# BiaBoard.net
KiCad netlist of a schematic drawn in EAGLE
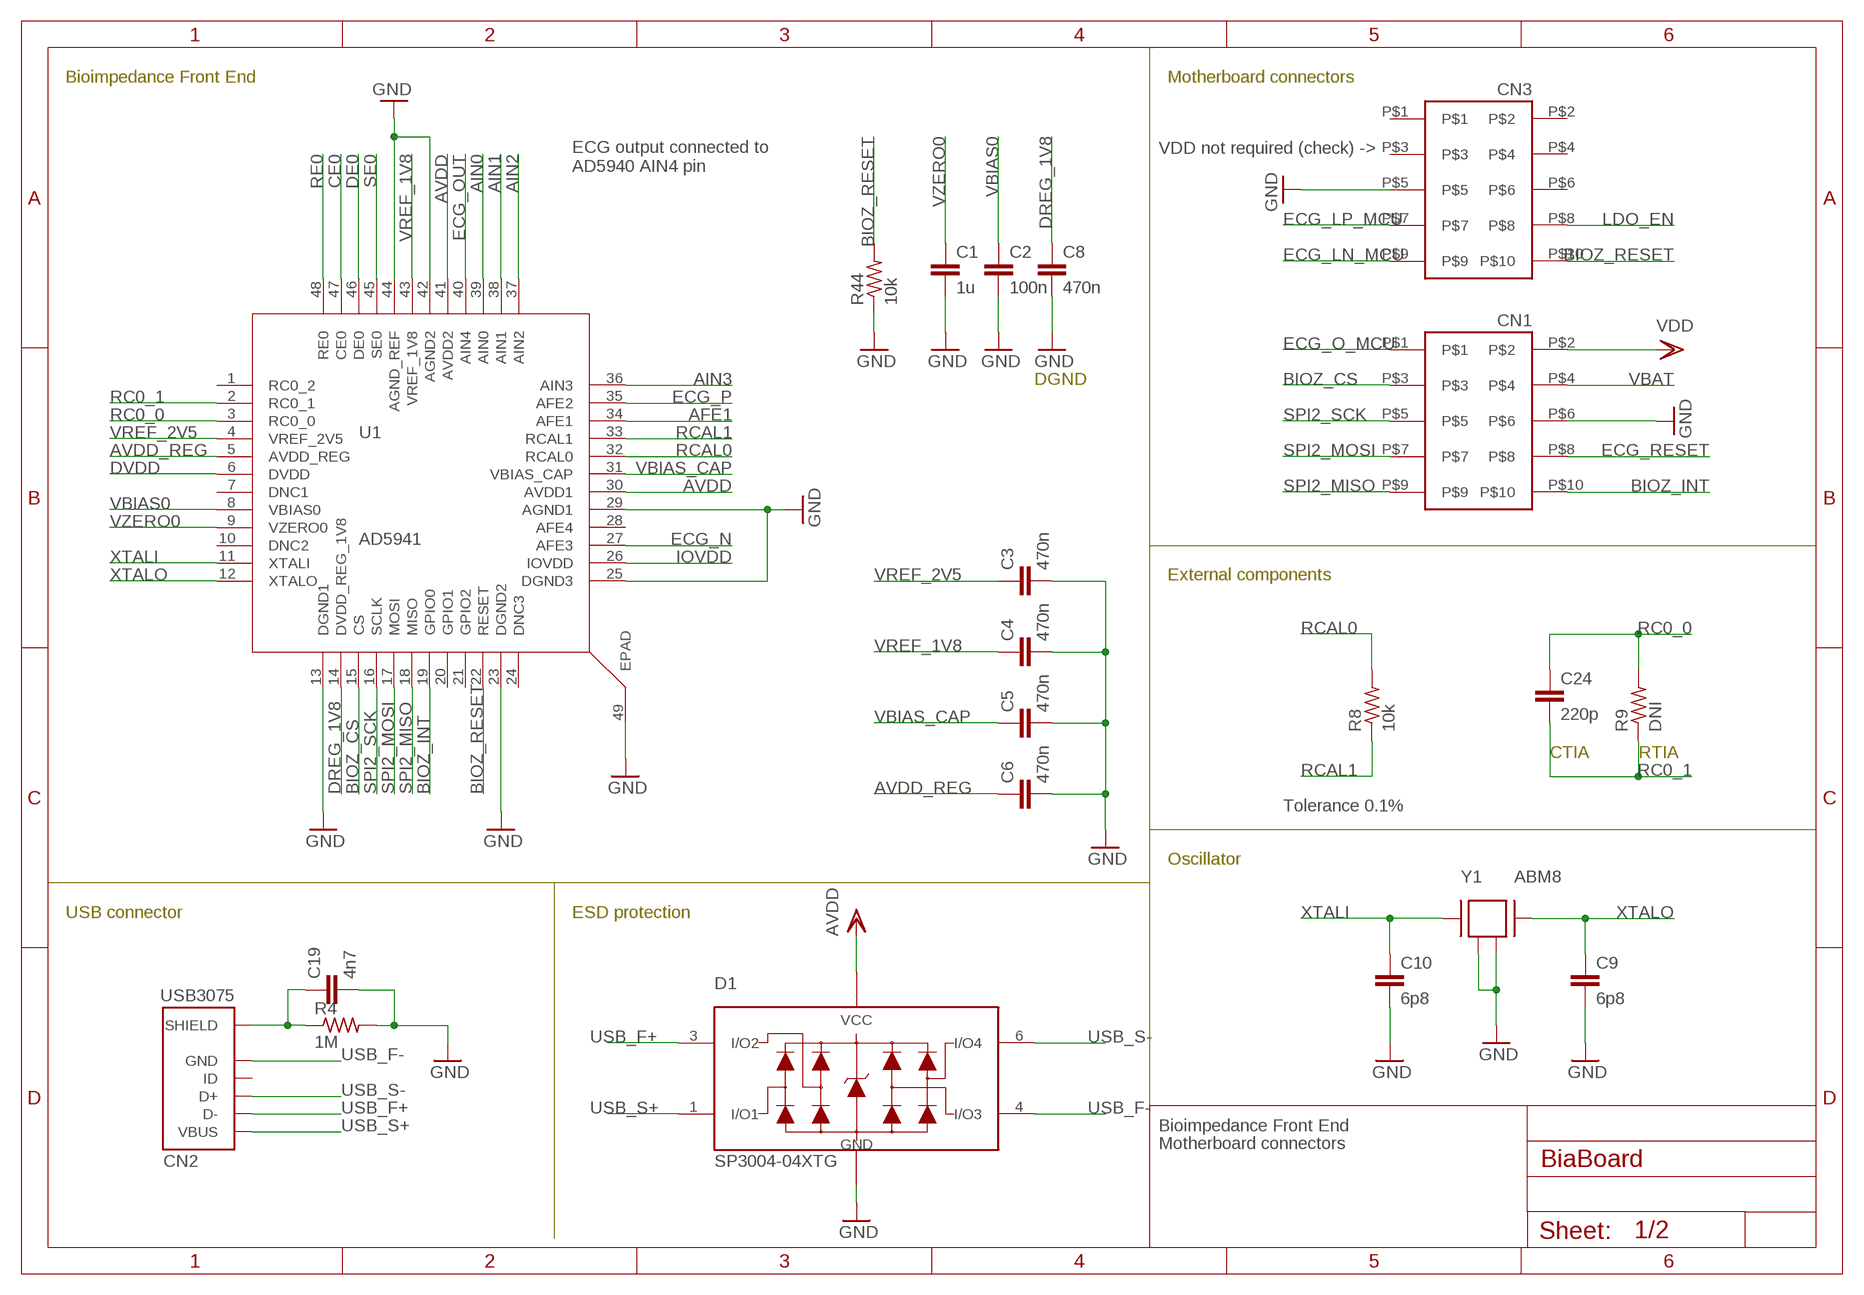
[diagram p0: schematic, sheet 1]
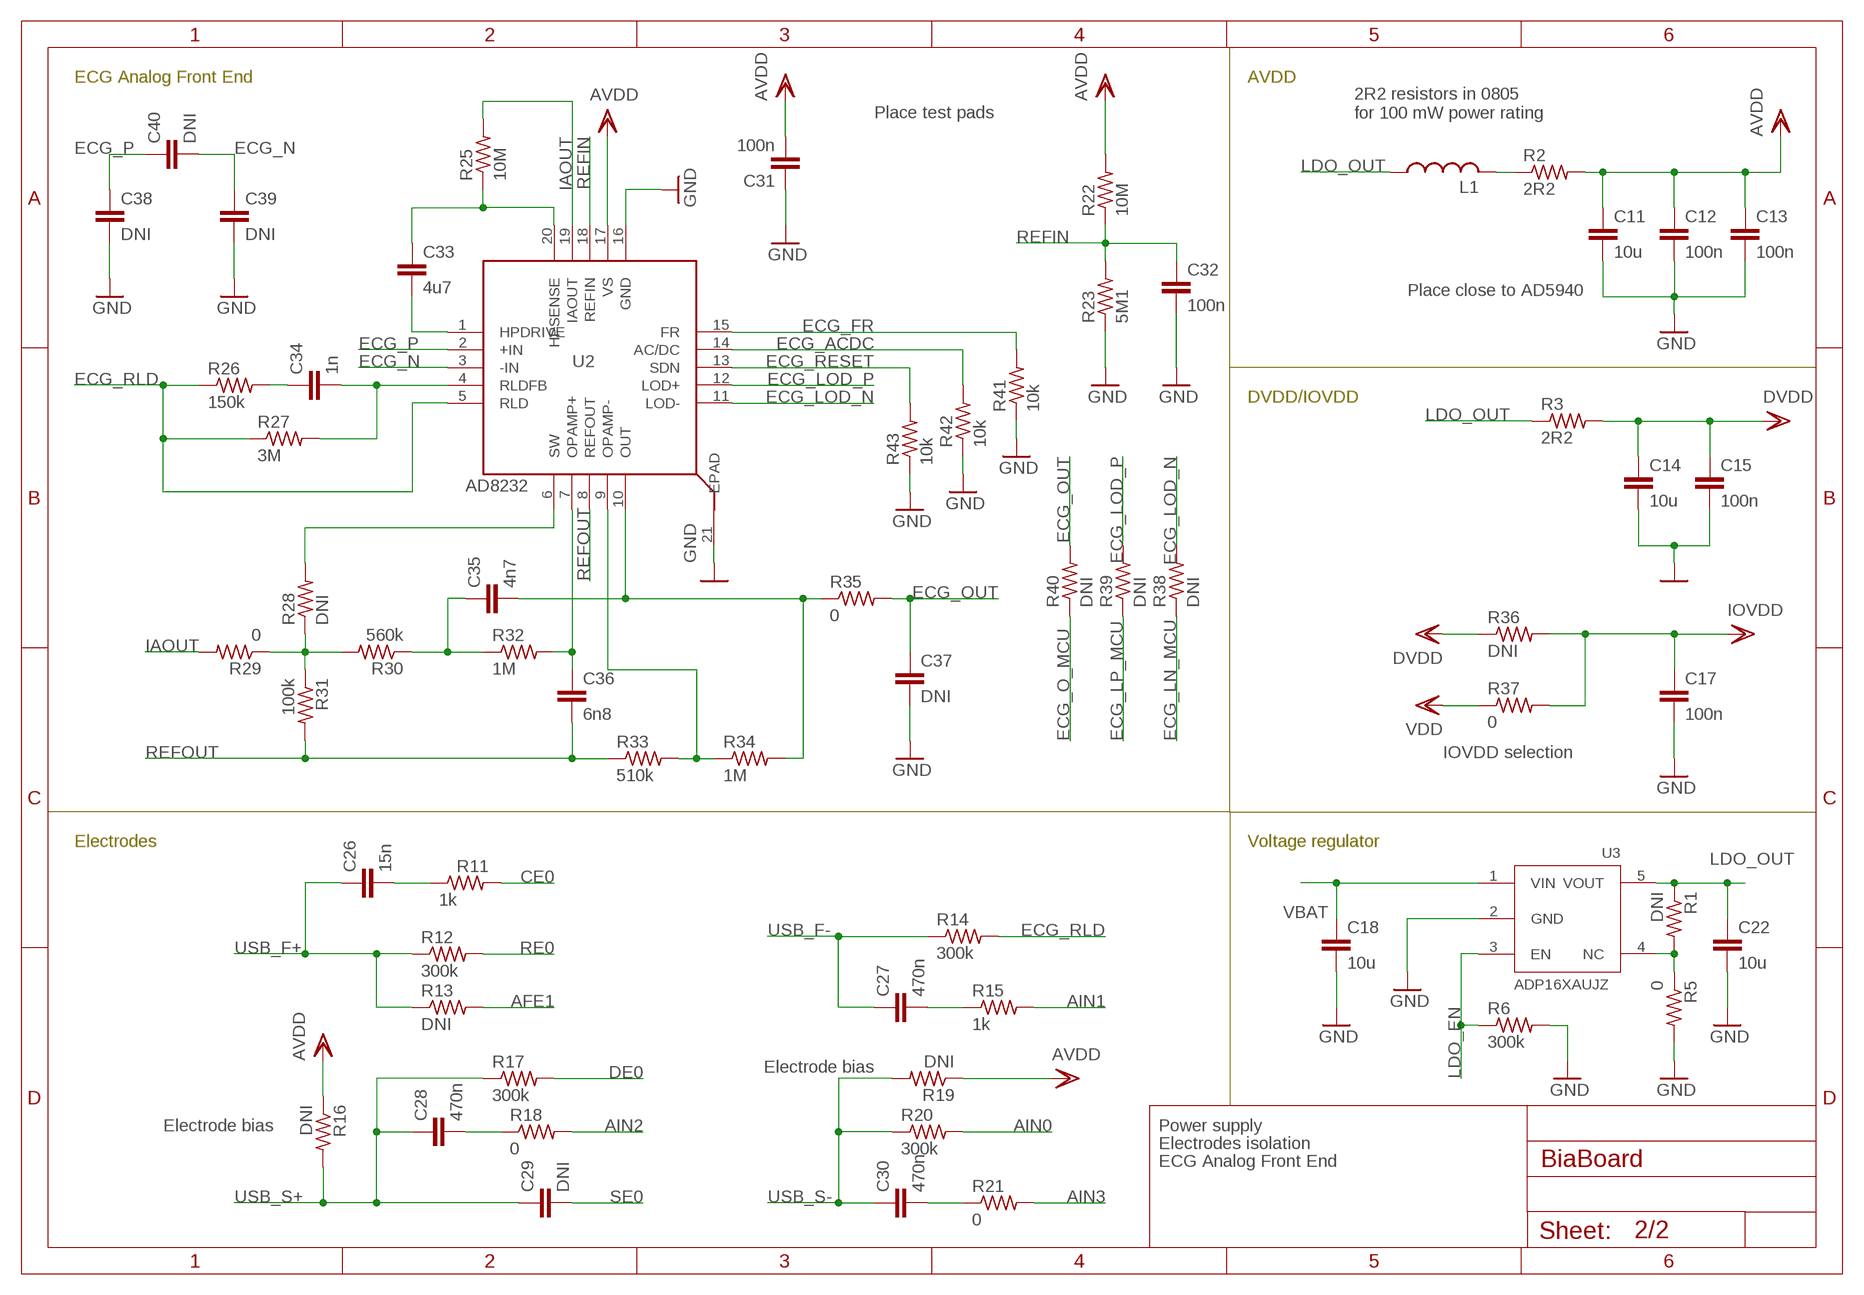
[diagram p1: schematic, sheet 2]

(export (version "E")
  (design (tool "Eeschema 10.0.6"))
  (components
    (comp (ref "C1")
      (value "1u")
      (footprint "eagle-import:C0402")
      (libsource (lib "eagle-import") (part "C0402"))
    )
    (comp (ref "C2")
      (value "100n")
      (footprint "eagle-import:C0402")
      (libsource (lib "eagle-import") (part "C0402"))
    )
    (comp (ref "C3")
      (value "470n")
      (footprint "eagle-import:C0402")
      (libsource (lib "eagle-import") (part "C0402"))
    )
    (comp (ref "C4")
      (value "470n")
      (footprint "eagle-import:C0402")
      (libsource (lib "eagle-import") (part "C0402"))
    )
    (comp (ref "C5")
      (value "470n")
      (footprint "eagle-import:C0402")
      (libsource (lib "eagle-import") (part "C0402"))
    )
    (comp (ref "C6")
      (value "470n")
      (footprint "eagle-import:C0402")
      (libsource (lib "eagle-import") (part "C0402"))
    )
    (comp (ref "C8")
      (value "470n")
      (footprint "eagle-import:C0402")
      (libsource (lib "eagle-import") (part "C0402"))
    )
    (comp (ref "C9")
      (value "6p8")
      (footprint "eagle-import:C0402")
      (libsource (lib "eagle-import") (part "C0402"))
    )
    (comp (ref "C10")
      (value "6p8")
      (footprint "eagle-import:C0402")
      (libsource (lib "eagle-import") (part "C0402"))
    )
    (comp (ref "C19")
      (value "4n7")
      (footprint "eagle-import:C0402")
      (libsource (lib "eagle-import") (part "C0402"))
    )
    (comp (ref "C24")
      (value "220p")
      (footprint "eagle-import:C0402")
      (libsource (lib "eagle-import") (part "C0402"))
    )
    (comp (ref "CN1")
      (value "FTSH-105TO")
      (footprint "eagle-import:FTSH-105-D")
      (libsource (lib "eagle-import") (part "FTSH-105TO"))
    )
    (comp (ref "CN2")
      (value "USB3075")
      (footprint "eagle-import:USB3075")
      (libsource (lib "eagle-import") (part "USB3075"))
    )
    (comp (ref "CN3")
      (value "FTSH-105TO")
      (footprint "eagle-import:FTSH-105-D")
      (libsource (lib "eagle-import") (part "FTSH-105TO"))
    )
    (comp (ref "D1")
      (value "SP3004-04XTG")
      (footprint "eagle-import:SOT50P160X60-6N")
      (libsource (lib "eagle-import") (part "SP3004-04XTG"))
    )
    (comp (ref "R4")
      (value "1M")
      (footprint "eagle-import:0402")
      (libsource (lib "eagle-import") (part "R0402"))
    )
    (comp (ref "R8")
      (value "10k")
      (footprint "eagle-import:0402")
      (fields (field (name "TOLERANCE") "0.1%"))
      (libsource (lib "eagle-import") (part "R0402"))
    )
    (comp (ref "R9")
      (value "DNI")
      (footprint "eagle-import:0402")
      (libsource (lib "eagle-import") (part "R0402"))
    )
    (comp (ref "R44")
      (value "10k")
      (footprint "eagle-import:0402")
      (libsource (lib "eagle-import") (part "R0402"))
    )
    (comp (ref "U1")
      (value "AD5941")
      (footprint "eagle-import:QFN50P700X700X80-49T510N")
      (libsource (lib "eagle-import") (part "AD5941"))
    )
    (comp (ref "Y1")
      (value "ABM8")
      (footprint "eagle-import:ABM8")
      (libsource (lib "eagle-import") (part "ABM8"))
    )
    (comp (ref "C11")
      (value "10u")
      (footprint "eagle-import:C0603")
      (libsource (lib "eagle-import") (part "C0603"))
    )
    (comp (ref "C12")
      (value "100n")
      (footprint "eagle-import:C0402")
      (libsource (lib "eagle-import") (part "C0402"))
    )
    (comp (ref "C13")
      (value "100n")
      (footprint "eagle-import:C0402")
      (libsource (lib "eagle-import") (part "C0402"))
    )
    (comp (ref "C14")
      (value "10u")
      (footprint "eagle-import:C0603")
      (libsource (lib "eagle-import") (part "C0603"))
    )
    (comp (ref "C15")
      (value "100n")
      (footprint "eagle-import:C0402")
      (libsource (lib "eagle-import") (part "C0402"))
    )
    (comp (ref "C17")
      (value "100n")
      (footprint "eagle-import:C0402")
      (libsource (lib "eagle-import") (part "C0402"))
    )
    (comp (ref "C18")
      (value "10u")
      (footprint "eagle-import:C0603")
      (libsource (lib "eagle-import") (part "C0603"))
    )
    (comp (ref "C22")
      (value "10u")
      (footprint "eagle-import:C0603")
      (libsource (lib "eagle-import") (part "C0603"))
    )
    (comp (ref "C26")
      (value "15n")
      (footprint "eagle-import:C0402")
      (libsource (lib "eagle-import") (part "C0402"))
    )
    (comp (ref "C27")
      (value "470n")
      (footprint "eagle-import:C0402")
      (libsource (lib "eagle-import") (part "C0402"))
    )
    (comp (ref "C28")
      (value "470n")
      (footprint "eagle-import:C0402")
      (libsource (lib "eagle-import") (part "C0402"))
    )
    (comp (ref "C29")
      (value "DNI")
      (footprint "eagle-import:C0402")
      (libsource (lib "eagle-import") (part "C0402"))
    )
    (comp (ref "C30")
      (value "470n")
      (footprint "eagle-import:C0402")
      (libsource (lib "eagle-import") (part "C0402"))
    )
    (comp (ref "C31")
      (value "100n")
      (footprint "eagle-import:C0402")
      (libsource (lib "eagle-import") (part "C0402"))
    )
    (comp (ref "C32")
      (value "100n")
      (footprint "eagle-import:C0402")
      (libsource (lib "eagle-import") (part "C0402"))
    )
    (comp (ref "C33")
      (value "4u7")
      (footprint "eagle-import:C0402")
      (libsource (lib "eagle-import") (part "C0402"))
    )
    (comp (ref "C34")
      (value "1n")
      (footprint "eagle-import:C0402")
      (libsource (lib "eagle-import") (part "C0402"))
    )
    (comp (ref "C35")
      (value "4n7")
      (footprint "eagle-import:C0402")
      (libsource (lib "eagle-import") (part "C0402"))
    )
    (comp (ref "C36")
      (value "6n8")
      (footprint "eagle-import:C0402")
      (libsource (lib "eagle-import") (part "C0402"))
    )
    (comp (ref "C37")
      (value "DNI")
      (footprint "eagle-import:C0603")
      (libsource (lib "eagle-import") (part "C0603"))
    )
    (comp (ref "C38")
      (value "DNI")
      (footprint "eagle-import:C0402")
      (libsource (lib "eagle-import") (part "C0402"))
    )
    (comp (ref "C39")
      (value "DNI")
      (footprint "eagle-import:C0402")
      (libsource (lib "eagle-import") (part "C0402"))
    )
    (comp (ref "C40")
      (value "DNI")
      (footprint "eagle-import:C0402")
      (libsource (lib "eagle-import") (part "C0402"))
    )
    (comp (ref "L1")
      (value "L0603")
      (footprint "eagle-import:0603")
      (libsource (lib "eagle-import") (part "L0603"))
    )
    (comp (ref "R1")
      (value "DNI")
      (footprint "eagle-import:0402")
      (libsource (lib "eagle-import") (part "R0402"))
    )
    (comp (ref "R2")
      (value "2R2")
      (footprint "eagle-import:0805")
      (libsource (lib "eagle-import") (part "R0805"))
    )
    (comp (ref "R3")
      (value "2R2")
      (footprint "eagle-import:0805")
      (libsource (lib "eagle-import") (part "R0805"))
    )
    (comp (ref "R5")
      (value "0")
      (footprint "eagle-import:0402")
      (libsource (lib "eagle-import") (part "R0402"))
    )
    (comp (ref "R6")
      (value "300k")
      (footprint "eagle-import:0402")
      (libsource (lib "eagle-import") (part "R0402"))
    )
    (comp (ref "R11")
      (value "1k")
      (footprint "eagle-import:0402")
      (libsource (lib "eagle-import") (part "R0402"))
    )
    (comp (ref "R12")
      (value "300k")
      (footprint "eagle-import:0402")
      (libsource (lib "eagle-import") (part "R0402"))
    )
    (comp (ref "R13")
      (value "DNI")
      (footprint "eagle-import:0402")
      (libsource (lib "eagle-import") (part "R0402"))
    )
    (comp (ref "R14")
      (value "300k")
      (footprint "eagle-import:0402")
      (libsource (lib "eagle-import") (part "R0402"))
    )
    (comp (ref "R15")
      (value "1k")
      (footprint "eagle-import:0402")
      (libsource (lib "eagle-import") (part "R0402"))
    )
    (comp (ref "R16")
      (value "DNI")
      (footprint "eagle-import:0402")
      (libsource (lib "eagle-import") (part "R0402"))
    )
    (comp (ref "R17")
      (value "300k")
      (footprint "eagle-import:0402")
      (libsource (lib "eagle-import") (part "R0402"))
    )
    (comp (ref "R18")
      (value "0")
      (footprint "eagle-import:0402")
      (libsource (lib "eagle-import") (part "R0402"))
    )
    (comp (ref "R19")
      (value "DNI")
      (footprint "eagle-import:0402")
      (libsource (lib "eagle-import") (part "R0402"))
    )
    (comp (ref "R20")
      (value "300k")
      (footprint "eagle-import:0402")
      (libsource (lib "eagle-import") (part "R0402"))
    )
    (comp (ref "R21")
      (value "0")
      (footprint "eagle-import:0402")
      (libsource (lib "eagle-import") (part "R0402"))
    )
    (comp (ref "R22")
      (value "10M")
      (footprint "eagle-import:0402")
      (libsource (lib "eagle-import") (part "R0402"))
    )
    (comp (ref "R23")
      (value "5M1")
      (footprint "eagle-import:0402")
      (libsource (lib "eagle-import") (part "R0402"))
    )
    (comp (ref "R25")
      (value "10M")
      (footprint "eagle-import:0402")
      (libsource (lib "eagle-import") (part "R0402"))
    )
    (comp (ref "R26")
      (value "150k")
      (footprint "eagle-import:0402")
      (libsource (lib "eagle-import") (part "R0402"))
    )
    (comp (ref "R27")
      (value "3M")
      (footprint "eagle-import:0402")
      (libsource (lib "eagle-import") (part "R0402"))
    )
    (comp (ref "R28")
      (value "DNI")
      (footprint "eagle-import:0402")
      (libsource (lib "eagle-import") (part "R0402"))
    )
    (comp (ref "R29")
      (value "0")
      (footprint "eagle-import:0402")
      (libsource (lib "eagle-import") (part "R0402"))
    )
    (comp (ref "R30")
      (value "560k")
      (footprint "eagle-import:0402")
      (libsource (lib "eagle-import") (part "R0402"))
    )
    (comp (ref "R31")
      (value "100k")
      (footprint "eagle-import:0603")
      (libsource (lib "eagle-import") (part "R0603"))
    )
    (comp (ref "R32")
      (value "1M")
      (footprint "eagle-import:0402")
      (libsource (lib "eagle-import") (part "R0402"))
    )
    (comp (ref "R33")
      (value "510k")
      (footprint "eagle-import:0402")
      (libsource (lib "eagle-import") (part "R0402"))
    )
    (comp (ref "R34")
      (value "1M")
      (footprint "eagle-import:0402")
      (libsource (lib "eagle-import") (part "R0402"))
    )
    (comp (ref "R35")
      (value "0")
      (footprint "eagle-import:0402")
      (libsource (lib "eagle-import") (part "R0402"))
    )
    (comp (ref "R36")
      (value "DNI")
      (footprint "eagle-import:0402")
      (libsource (lib "eagle-import") (part "R0402"))
    )
    (comp (ref "R37")
      (value "0")
      (footprint "eagle-import:0402")
      (libsource (lib "eagle-import") (part "R0402"))
    )
    (comp (ref "R38")
      (value "DNI")
      (footprint "eagle-import:0402")
      (libsource (lib "eagle-import") (part "R0402"))
    )
    (comp (ref "R39")
      (value "DNI")
      (footprint "eagle-import:0402")
      (libsource (lib "eagle-import") (part "R0402"))
    )
    (comp (ref "R40")
      (value "DNI")
      (footprint "eagle-import:0402")
      (libsource (lib "eagle-import") (part "R0402"))
    )
    (comp (ref "R41")
      (value "10k")
      (footprint "eagle-import:0402")
      (libsource (lib "eagle-import") (part "R0402"))
    )
    (comp (ref "R42")
      (value "10k")
      (footprint "eagle-import:0402")
      (libsource (lib "eagle-import") (part "R0402"))
    )
    (comp (ref "R43")
      (value "10k")
      (footprint "eagle-import:0402")
      (libsource (lib "eagle-import") (part "R0402"))
    )
    (comp (ref "U2")
      (value "AD8232")
      (footprint "eagle-import:QFN50P400X400X75-21T260N")
      (libsource (lib "eagle-import") (part "AD8232"))
    )
    (comp (ref "U3")
      (value "ADP16XAUJZ")
      (footprint "eagle-import:TSOT23-5L")
      (libsource (lib "eagle-import") (part "ADP16XAUJZ"))
    )
  )
  (nets
    (net (code "1") (name "AFE1") (class "Default")
      (node (ref "R13") (pin "P$2") (pinfunction "2_P$2") (pintype "passive"))
      (node (ref "U1") (pin "34") (pinfunction "AFE1_34") (pintype "bidirectional"))
    )
    (net (code "2") (name "AIN0") (class "Default")
      (node (ref "R20") (pin "P$2") (pinfunction "2_P$2") (pintype "passive"))
      (node (ref "U1") (pin "39") (pinfunction "AIN0_39") (pintype "bidirectional"))
    )
    (net (code "3") (name "AIN1") (class "Default")
      (node (ref "R15") (pin "P$2") (pinfunction "2_P$2") (pintype "passive"))
      (node (ref "U1") (pin "38") (pinfunction "AIN1_38") (pintype "bidirectional"))
    )
    (net (code "4") (name "AIN2") (class "Default")
      (node (ref "R18") (pin "P$2") (pinfunction "2_P$2") (pintype "passive"))
      (node (ref "U1") (pin "37") (pinfunction "AIN2_37") (pintype "bidirectional"))
    )
    (net (code "5") (name "AIN3") (class "Default")
      (node (ref "R21") (pin "P$2") (pinfunction "2_P$2") (pintype "passive"))
      (node (ref "U1") (pin "36") (pinfunction "AIN3_36") (pintype "bidirectional"))
    )
    (net (code "6") (name "AVDD") (class "Default")
      (node (ref "C11") (pin "P$1") (pinfunction "1_P$1") (pintype "passive"))
      (node (ref "C12") (pin "P$1") (pinfunction "1_P$1") (pintype "passive"))
      (node (ref "C13") (pin "P$1") (pinfunction "1_P$1") (pintype "passive"))
      (node (ref "C31") (pin "P$2") (pinfunction "2_P$2") (pintype "passive"))
      (node (ref "D1") (pin "5") (pinfunction "VCC_5") (pintype "bidirectional"))
      (node (ref "R16") (pin "P$1") (pinfunction "1_P$1") (pintype "passive"))
      (node (ref "R19") (pin "P$1") (pinfunction "1_P$1") (pintype "passive"))
      (node (ref "R2") (pin "P$2") (pinfunction "2_P$2") (pintype "passive"))
      (node (ref "R22") (pin "P$2") (pinfunction "2_P$2") (pintype "passive"))
      (node (ref "U1") (pin "30") (pinfunction "AVDD1_30") (pintype "bidirectional"))
      (node (ref "U1") (pin "41") (pinfunction "AVDD2_41") (pintype "bidirectional"))
      (node (ref "U2") (pin "17") (pinfunction "VS_17") (pintype "bidirectional"))
    )
    (net (code "7") (name "AVDD_REG") (class "Default")
      (node (ref "C6") (pin "P$1") (pinfunction "1_P$1") (pintype "passive"))
      (node (ref "U1") (pin "5") (pinfunction "AVDD_REG_5") (pintype "bidirectional"))
    )
    (net (code "8") (name "BIOZ_CS") (class "Default")
      (node (ref "CN1") (pin "P$3") (pinfunction "P$3_P$3") (pintype "bidirectional"))
      (node (ref "U1") (pin "15") (pinfunction "CS_15") (pintype "bidirectional"))
    )
    (net (code "9") (name "BIOZ_INT") (class "Default")
      (node (ref "CN1") (pin "P$10") (pinfunction "P$10_P$10") (pintype "bidirectional"))
      (node (ref "U1") (pin "19") (pinfunction "GPIO0_19") (pintype "bidirectional"))
    )
    (net (code "10") (name "BIOZ_RESET") (class "Default")
      (node (ref "CN3") (pin "P$10") (pinfunction "P$10_P$10") (pintype "bidirectional"))
      (node (ref "R44") (pin "P$2") (pinfunction "2_P$2") (pintype "passive"))
      (node (ref "U1") (pin "22") (pinfunction "RESET_22") (pintype "bidirectional"))
    )
    (net (code "11") (name "CE0") (class "Default")
      (node (ref "R11") (pin "P$2") (pinfunction "2_P$2") (pintype "passive"))
      (node (ref "U1") (pin "47") (pinfunction "CE0_47") (pintype "bidirectional"))
    )
    (net (code "12") (name "DE0") (class "Default")
      (node (ref "R17") (pin "P$2") (pinfunction "2_P$2") (pintype "passive"))
      (node (ref "U1") (pin "46") (pinfunction "DE0_46") (pintype "bidirectional"))
    )
    (net (code "13") (name "DREG_1V8") (class "Default")
      (node (ref "C8") (pin "P$1") (pinfunction "1_P$1") (pintype "passive"))
      (node (ref "U1") (pin "14") (pinfunction "DVDD_REG_1V8_14") (pintype "bidirectional"))
    )
    (net (code "14") (name "DVDD") (class "Default")
      (node (ref "C14") (pin "P$1") (pinfunction "1_P$1") (pintype "passive"))
      (node (ref "C15") (pin "P$1") (pinfunction "1_P$1") (pintype "passive"))
      (node (ref "R3") (pin "P$2") (pinfunction "2_P$2") (pintype "passive"))
      (node (ref "R36") (pin "P$1") (pinfunction "1_P$1") (pintype "passive"))
      (node (ref "U1") (pin "6") (pinfunction "DVDD_6") (pintype "bidirectional"))
    )
    (net (code "15") (name "ECG_ACDC") (class "Default")
      (node (ref "R42") (pin "P$2") (pinfunction "2_P$2") (pintype "passive"))
      (node (ref "U2") (pin "14") (pinfunction "AC/DC_14") (pintype "bidirectional"))
    )
    (net (code "16") (name "ECG_FR") (class "Default")
      (node (ref "R41") (pin "P$2") (pinfunction "2_P$2") (pintype "passive"))
      (node (ref "U2") (pin "15") (pinfunction "FR_15") (pintype "bidirectional"))
    )
    (net (code "17") (name "ECG_LN_MCU") (class "Default")
      (node (ref "CN3") (pin "P$9") (pinfunction "P$9_P$9") (pintype "bidirectional"))
      (node (ref "R38") (pin "P$1") (pinfunction "1_P$1") (pintype "passive"))
    )
    (net (code "18") (name "ECG_LOD_N") (class "Default")
      (node (ref "R38") (pin "P$2") (pinfunction "2_P$2") (pintype "passive"))
      (node (ref "U2") (pin "11") (pinfunction "LOD-_11") (pintype "bidirectional"))
    )
    (net (code "19") (name "ECG_LOD_P") (class "Default")
      (node (ref "R39") (pin "P$2") (pinfunction "2_P$2") (pintype "passive"))
      (node (ref "U2") (pin "12") (pinfunction "LOD+_12") (pintype "bidirectional"))
    )
    (net (code "20") (name "ECG_LP_MCU") (class "Default")
      (node (ref "CN3") (pin "P$7") (pinfunction "P$7_P$7") (pintype "bidirectional"))
      (node (ref "R39") (pin "P$1") (pinfunction "1_P$1") (pintype "passive"))
    )
    (net (code "21") (name "ECG_N") (class "Default")
      (node (ref "C39") (pin "P$1") (pinfunction "1_P$1") (pintype "passive"))
      (node (ref "C40") (pin "P$2") (pinfunction "2_P$2") (pintype "passive"))
      (node (ref "U1") (pin "27") (pinfunction "AFE3_27") (pintype "bidirectional"))
      (node (ref "U2") (pin "3") (pinfunction "-IN_3") (pintype "bidirectional"))
    )
    (net (code "22") (name "ECG_OUT") (class "Default")
      (node (ref "C37") (pin "P$1") (pinfunction "1_P$1") (pintype "passive"))
      (node (ref "R35") (pin "P$2") (pinfunction "2_P$2") (pintype "passive"))
      (node (ref "R40") (pin "P$2") (pinfunction "2_P$2") (pintype "passive"))
      (node (ref "U1") (pin "40") (pinfunction "AIN4_40") (pintype "bidirectional"))
    )
    (net (code "23") (name "ECG_O_MCU") (class "Default")
      (node (ref "CN1") (pin "P$1") (pinfunction "P$1_P$1") (pintype "bidirectional"))
      (node (ref "R40") (pin "P$1") (pinfunction "1_P$1") (pintype "passive"))
    )
    (net (code "24") (name "ECG_P") (class "Default")
      (node (ref "C38") (pin "P$1") (pinfunction "1_P$1") (pintype "passive"))
      (node (ref "C40") (pin "P$1") (pinfunction "1_P$1") (pintype "passive"))
      (node (ref "U1") (pin "35") (pinfunction "AFE2_35") (pintype "bidirectional"))
      (node (ref "U2") (pin "2") (pinfunction "+IN_2") (pintype "bidirectional"))
    )
    (net (code "25") (name "ECG_RESET") (class "Default")
      (node (ref "CN1") (pin "P$8") (pinfunction "P$8_P$8") (pintype "bidirectional"))
      (node (ref "R43") (pin "P$2") (pinfunction "2_P$2") (pintype "passive"))
      (node (ref "U2") (pin "13") (pinfunction "SDN_13") (pintype "bidirectional"))
    )
    (net (code "26") (name "ECG_RLD") (class "Default")
      (node (ref "R14") (pin "P$2") (pinfunction "2_P$2") (pintype "passive"))
      (node (ref "R26") (pin "P$1") (pinfunction "1_P$1") (pintype "passive"))
      (node (ref "R27") (pin "P$1") (pinfunction "1_P$1") (pintype "passive"))
      (node (ref "U2") (pin "5") (pinfunction "RLD_5") (pintype "bidirectional"))
    )
    (net (code "27") (name "GND") (class "Default")
      (node (ref "C1") (pin "P$2") (pinfunction "2_P$2") (pintype "passive"))
      (node (ref "C10") (pin "P$2") (pinfunction "2_P$2") (pintype "passive"))
      (node (ref "C11") (pin "P$2") (pinfunction "2_P$2") (pintype "passive"))
      (node (ref "C12") (pin "P$2") (pinfunction "2_P$2") (pintype "passive"))
      (node (ref "C13") (pin "P$2") (pinfunction "2_P$2") (pintype "passive"))
      (node (ref "C14") (pin "P$2") (pinfunction "2_P$2") (pintype "passive"))
      (node (ref "C15") (pin "P$2") (pinfunction "2_P$2") (pintype "passive"))
      (node (ref "C17") (pin "P$2") (pinfunction "2_P$2") (pintype "passive"))
      (node (ref "C18") (pin "P$2") (pinfunction "2_P$2") (pintype "passive"))
      (node (ref "C19") (pin "P$2") (pinfunction "2_P$2") (pintype "passive"))
      (node (ref "C2") (pin "P$2") (pinfunction "2_P$2") (pintype "passive"))
      (node (ref "C22") (pin "P$2") (pinfunction "2_P$2") (pintype "passive"))
      (node (ref "C3") (pin "P$2") (pinfunction "2_P$2") (pintype "passive"))
      (node (ref "C31") (pin "P$1") (pinfunction "1_P$1") (pintype "passive"))
      (node (ref "C32") (pin "P$2") (pinfunction "2_P$2") (pintype "passive"))
      (node (ref "C37") (pin "P$2") (pinfunction "2_P$2") (pintype "passive"))
      (node (ref "C38") (pin "P$2") (pinfunction "2_P$2") (pintype "passive"))
      (node (ref "C39") (pin "P$2") (pinfunction "2_P$2") (pintype "passive"))
      (node (ref "C4") (pin "P$2") (pinfunction "2_P$2") (pintype "passive"))
      (node (ref "C5") (pin "P$2") (pinfunction "2_P$2") (pintype "passive"))
      (node (ref "C6") (pin "P$2") (pinfunction "2_P$2") (pintype "passive"))
      (node (ref "C8") (pin "P$2") (pinfunction "2_P$2") (pintype "passive"))
      (node (ref "C9") (pin "P$2") (pinfunction "2_P$2") (pintype "passive"))
      (node (ref "CN1") (pin "P$6") (pinfunction "P$6_P$6") (pintype "bidirectional"))
      (node (ref "CN3") (pin "P$5") (pinfunction "P$5_P$5") (pintype "bidirectional"))
      (node (ref "D1") (pin "2") (pinfunction "GND_2") (pintype "bidirectional"))
      (node (ref "R23") (pin "P$1") (pinfunction "1_P$1") (pintype "passive"))
      (node (ref "R4") (pin "P$2") (pinfunction "2_P$2") (pintype "passive"))
      (node (ref "R41") (pin "P$1") (pinfunction "1_P$1") (pintype "passive"))
      (node (ref "R42") (pin "P$1") (pinfunction "1_P$1") (pintype "passive"))
      (node (ref "R43") (pin "P$1") (pinfunction "1_P$1") (pintype "passive"))
      (node (ref "R44") (pin "P$1") (pinfunction "1_P$1") (pintype "passive"))
      (node (ref "R5") (pin "P$2") (pinfunction "2_P$2") (pintype "passive"))
      (node (ref "R6") (pin "P$2") (pinfunction "2_P$2") (pintype "passive"))
      (node (ref "U1") (pin "13") (pinfunction "DGND1_13") (pintype "bidirectional"))
      (node (ref "U1") (pin "23") (pinfunction "DGND2_23") (pintype "bidirectional"))
      (node (ref "U1") (pin "25") (pinfunction "DGND3_25") (pintype "bidirectional"))
      (node (ref "U1") (pin "29") (pinfunction "AGND1_29") (pintype "bidirectional"))
      (node (ref "U1") (pin "42") (pinfunction "AGND2_42") (pintype "bidirectional"))
      (node (ref "U1") (pin "44") (pinfunction "AGND_REF_44") (pintype "bidirectional"))
      (node (ref "U1") (pin "49") (pinfunction "EPAD_49") (pintype "bidirectional"))
      (node (ref "U2") (pin "16") (pinfunction "GND_16") (pintype "bidirectional"))
      (node (ref "U2") (pin "21") (pinfunction "EPAD_21") (pintype "bidirectional"))
      (node (ref "U3") (pin "2") (pinfunction "GND_2") (pintype "bidirectional"))
      (node (ref "Y1") (pin "P$2") (pinfunction "2_P$2") (pintype "passive"))
      (node (ref "Y1") (pin "P$4") (pinfunction "4_P$4") (pintype "passive"))
    )
    (net (code "28") (name "IAOUT") (class "Default")
      (node (ref "R25") (pin "P$2") (pinfunction "2_P$2") (pintype "passive"))
      (node (ref "R29") (pin "P$2") (pinfunction "2_P$2") (pintype "passive"))
      (node (ref "U2") (pin "19") (pinfunction "IAOUT_19") (pintype "bidirectional"))
    )
    (net (code "29") (name "IOVDD") (class "Default")
      (node (ref "C17") (pin "P$1") (pinfunction "1_P$1") (pintype "passive"))
      (node (ref "R36") (pin "P$2") (pinfunction "2_P$2") (pintype "passive"))
      (node (ref "R37") (pin "P$2") (pinfunction "2_P$2") (pintype "passive"))
      (node (ref "U1") (pin "26") (pinfunction "IOVDD_26") (pintype "bidirectional"))
    )
    (net (code "30") (name "LDO_EN") (class "Default")
      (node (ref "CN3") (pin "P$8") (pinfunction "P$8_P$8") (pintype "bidirectional"))
      (node (ref "R6") (pin "P$1") (pinfunction "1_P$1") (pintype "passive"))
      (node (ref "U3") (pin "3") (pinfunction "EN_3") (pintype "bidirectional"))
    )
    (net (code "31") (name "LDO_OUT") (class "Default")
      (node (ref "C22") (pin "P$1") (pinfunction "1_P$1") (pintype "passive"))
      (node (ref "L1") (pin "P$1") (pinfunction "1_P$1") (pintype "passive"))
      (node (ref "R1") (pin "P$1") (pinfunction "1_P$1") (pintype "passive"))
      (node (ref "R3") (pin "P$1") (pinfunction "1_P$1") (pintype "passive"))
      (node (ref "U3") (pin "5") (pinfunction "VOUT_5") (pintype "bidirectional"))
    )
    (net (code "32") (name "Net-(C19-1)") (class "Default")
      (node (ref "C19") (pin "P$1") (pinfunction "1_P$1") (pintype "passive"))
      (node (ref "CN2") (pin "G1") (pinfunction "SHIELD_G1") (pintype "passive"))
      (node (ref "CN2") (pin "G2") (pinfunction "SHIELD_G2") (pintype "passive"))
      (node (ref "CN2") (pin "G3") (pinfunction "SHIELD_G3") (pintype "passive"))
      (node (ref "CN2") (pin "G4") (pinfunction "SHIELD_G4") (pintype "passive"))
      (node (ref "CN2") (pin "G5") (pinfunction "SHIELD_G5") (pintype "passive"))
      (node (ref "CN2") (pin "G6") (pinfunction "SHIELD_G6") (pintype "passive"))
      (node (ref "R4") (pin "P$1") (pinfunction "1_P$1") (pintype "passive"))
    )
    (net (code "33") (name "Net-(C26-2)") (class "Default")
      (node (ref "C26") (pin "P$2") (pinfunction "2_P$2") (pintype "passive"))
      (node (ref "R11") (pin "P$1") (pinfunction "1_P$1") (pintype "passive"))
    )
    (net (code "34") (name "Net-(C27-2)") (class "Default")
      (node (ref "C27") (pin "P$2") (pinfunction "2_P$2") (pintype "passive"))
      (node (ref "R15") (pin "P$1") (pinfunction "1_P$1") (pintype "passive"))
    )
    (net (code "35") (name "Net-(C28-2)") (class "Default")
      (node (ref "C28") (pin "P$2") (pinfunction "2_P$2") (pintype "passive"))
      (node (ref "R18") (pin "P$1") (pinfunction "1_P$1") (pintype "passive"))
    )
    (net (code "36") (name "Net-(C30-2)") (class "Default")
      (node (ref "C30") (pin "P$2") (pinfunction "2_P$2") (pintype "passive"))
      (node (ref "R21") (pin "P$1") (pinfunction "1_P$1") (pintype "passive"))
    )
    (net (code "37") (name "Net-(C33-1)") (class "Default")
      (node (ref "C33") (pin "P$1") (pinfunction "1_P$1") (pintype "passive"))
      (node (ref "R25") (pin "P$1") (pinfunction "1_P$1") (pintype "passive"))
      (node (ref "U2") (pin "20") (pinfunction "HPSENSE_20") (pintype "bidirectional"))
    )
    (net (code "38") (name "Net-(C33-2)") (class "Default")
      (node (ref "C33") (pin "P$2") (pinfunction "2_P$2") (pintype "passive"))
      (node (ref "U2") (pin "1") (pinfunction "HPDRIVE_1") (pintype "bidirectional"))
    )
    (net (code "39") (name "Net-(C34-1)") (class "Default")
      (node (ref "C34") (pin "P$1") (pinfunction "1_P$1") (pintype "passive"))
      (node (ref "R26") (pin "P$2") (pinfunction "2_P$2") (pintype "passive"))
    )
    (net (code "40") (name "Net-(C34-2)") (class "Default")
      (node (ref "C34") (pin "P$2") (pinfunction "2_P$2") (pintype "passive"))
      (node (ref "R27") (pin "P$2") (pinfunction "2_P$2") (pintype "passive"))
      (node (ref "U2") (pin "4") (pinfunction "RLDFB_4") (pintype "bidirectional"))
    )
    (net (code "41") (name "Net-(C35-1)") (class "Default")
      (node (ref "C35") (pin "P$1") (pinfunction "1_P$1") (pintype "passive"))
      (node (ref "R30") (pin "P$1") (pinfunction "1_P$1") (pintype "passive"))
      (node (ref "R32") (pin "P$1") (pinfunction "1_P$1") (pintype "passive"))
    )
    (net (code "42") (name "Net-(C35-2)") (class "Default")
      (node (ref "C35") (pin "P$2") (pinfunction "2_P$2") (pintype "passive"))
      (node (ref "R34") (pin "P$2") (pinfunction "2_P$2") (pintype "passive"))
      (node (ref "R35") (pin "P$1") (pinfunction "1_P$1") (pintype "passive"))
      (node (ref "U2") (pin "10") (pinfunction "OUT_10") (pintype "bidirectional"))
    )
    (net (code "43") (name "Net-(C36-1)") (class "Default")
      (node (ref "C36") (pin "P$1") (pinfunction "1_P$1") (pintype "passive"))
      (node (ref "R32") (pin "P$2") (pinfunction "2_P$2") (pintype "passive"))
      (node (ref "U2") (pin "7") (pinfunction "OPAMP+_7") (pintype "bidirectional"))
    )
    (net (code "44") (name "Net-(L1-2)") (class "Default")
      (node (ref "L1") (pin "P$2") (pinfunction "2_P$2") (pintype "passive"))
      (node (ref "R2") (pin "P$1") (pinfunction "1_P$1") (pintype "passive"))
    )
    (net (code "45") (name "Net-(R1-2)") (class "Default")
      (node (ref "R1") (pin "P$2") (pinfunction "2_P$2") (pintype "passive"))
      (node (ref "R5") (pin "P$1") (pinfunction "1_P$1") (pintype "passive"))
      (node (ref "U3") (pin "4") (pinfunction "NC_4") (pintype "bidirectional"))
    )
    (net (code "46") (name "Net-(R28-1)") (class "Default")
      (node (ref "R28") (pin "P$1") (pinfunction "1_P$1") (pintype "passive"))
      (node (ref "R29") (pin "P$1") (pinfunction "1_P$1") (pintype "passive"))
      (node (ref "R30") (pin "P$2") (pinfunction "2_P$2") (pintype "passive"))
      (node (ref "R31") (pin "P$1") (pinfunction "1_P$1") (pintype "passive"))
    )
    (net (code "47") (name "Net-(R28-2)") (class "Default")
      (node (ref "R28") (pin "P$2") (pinfunction "2_P$2") (pintype "passive"))
      (node (ref "U2") (pin "6") (pinfunction "SW_6") (pintype "bidirectional"))
    )
    (net (code "48") (name "Net-(R33-2)") (class "Default")
      (node (ref "R33") (pin "P$2") (pinfunction "2_P$2") (pintype "passive"))
      (node (ref "R34") (pin "P$1") (pinfunction "1_P$1") (pintype "passive"))
      (node (ref "U2") (pin "9") (pinfunction "OPAMP-_9") (pintype "bidirectional"))
    )
    (net (code "49") (name "RC0_0") (class "Default")
      (node (ref "C24") (pin "P$1") (pinfunction "1_P$1") (pintype "passive"))
      (node (ref "R9") (pin "P$2") (pinfunction "2_P$2") (pintype "passive"))
      (node (ref "U1") (pin "3") (pinfunction "RC0_0_3") (pintype "bidirectional"))
    )
    (net (code "50") (name "RC0_1") (class "Default")
      (node (ref "C24") (pin "P$2") (pinfunction "2_P$2") (pintype "passive"))
      (node (ref "R9") (pin "P$1") (pinfunction "1_P$1") (pintype "passive"))
      (node (ref "U1") (pin "2") (pinfunction "RC0_1_2") (pintype "bidirectional"))
    )
    (net (code "51") (name "RCAL0") (class "Default")
      (node (ref "R8") (pin "P$2") (pinfunction "2_P$2") (pintype "passive"))
      (node (ref "U1") (pin "32") (pinfunction "RCAL0_32") (pintype "bidirectional"))
    )
    (net (code "52") (name "RCAL1") (class "Default")
      (node (ref "R8") (pin "P$1") (pinfunction "1_P$1") (pintype "passive"))
      (node (ref "U1") (pin "33") (pinfunction "RCAL1_33") (pintype "bidirectional"))
    )
    (net (code "53") (name "RE0") (class "Default")
      (node (ref "R12") (pin "P$2") (pinfunction "2_P$2") (pintype "passive"))
      (node (ref "U1") (pin "48") (pinfunction "RE0_48") (pintype "bidirectional"))
    )
    (net (code "54") (name "REFIN") (class "Default")
      (node (ref "C32") (pin "P$1") (pinfunction "1_P$1") (pintype "passive"))
      (node (ref "R22") (pin "P$1") (pinfunction "1_P$1") (pintype "passive"))
      (node (ref "R23") (pin "P$2") (pinfunction "2_P$2") (pintype "passive"))
      (node (ref "U2") (pin "18") (pinfunction "REFIN_18") (pintype "bidirectional"))
    )
    (net (code "55") (name "REFOUT") (class "Default")
      (node (ref "C36") (pin "P$2") (pinfunction "2_P$2") (pintype "passive"))
      (node (ref "R31") (pin "P$2") (pinfunction "2_P$2") (pintype "passive"))
      (node (ref "R33") (pin "P$1") (pinfunction "1_P$1") (pintype "passive"))
      (node (ref "U2") (pin "8") (pinfunction "REFOUT_8") (pintype "bidirectional"))
    )
    (net (code "56") (name "SE0") (class "Default")
      (node (ref "C29") (pin "P$2") (pinfunction "2_P$2") (pintype "passive"))
      (node (ref "U1") (pin "45") (pinfunction "SE0_45") (pintype "bidirectional"))
    )
    (net (code "57") (name "SPI2_MISO") (class "Default")
      (node (ref "CN1") (pin "P$9") (pinfunction "P$9_P$9") (pintype "bidirectional"))
      (node (ref "U1") (pin "18") (pinfunction "MISO_18") (pintype "bidirectional"))
    )
    (net (code "58") (name "SPI2_MOSI") (class "Default")
      (node (ref "CN1") (pin "P$7") (pinfunction "P$7_P$7") (pintype "bidirectional"))
      (node (ref "U1") (pin "17") (pinfunction "MOSI_17") (pintype "bidirectional"))
    )
    (net (code "59") (name "SPI2_SCK") (class "Default")
      (node (ref "CN1") (pin "P$5") (pinfunction "P$5_P$5") (pintype "bidirectional"))
      (node (ref "U1") (pin "16") (pinfunction "SCLK_16") (pintype "bidirectional"))
    )
    (net (code "60") (name "USB_F+") (class "Default")
      (node (ref "C26") (pin "P$1") (pinfunction "1_P$1") (pintype "passive"))
      (node (ref "CN2") (pin "P2") (pinfunction "D-_P2") (pintype "bidirectional"))
      (node (ref "D1") (pin "3") (pinfunction "I/O2_3") (pintype "bidirectional"))
      (node (ref "R12") (pin "P$1") (pinfunction "1_P$1") (pintype "passive"))
      (node (ref "R13") (pin "P$1") (pinfunction "1_P$1") (pintype "passive"))
    )
    (net (code "61") (name "USB_F-") (class "Default")
      (node (ref "C27") (pin "P$1") (pinfunction "1_P$1") (pintype "passive"))
      (node (ref "CN2") (pin "P5") (pinfunction "GND_P5") (pintype "power_in"))
      (node (ref "D1") (pin "4") (pinfunction "I/O3_4") (pintype "bidirectional"))
      (node (ref "R14") (pin "P$1") (pinfunction "1_P$1") (pintype "passive"))
    )
    (net (code "62") (name "USB_S+") (class "Default")
      (node (ref "C28") (pin "P$1") (pinfunction "1_P$1") (pintype "passive"))
      (node (ref "C29") (pin "P$1") (pinfunction "1_P$1") (pintype "passive"))
      (node (ref "CN2") (pin "P1") (pinfunction "VBUS_P1") (pintype "power_in"))
      (node (ref "D1") (pin "1") (pinfunction "I/O1_1") (pintype "bidirectional"))
      (node (ref "R16") (pin "P$2") (pinfunction "2_P$2") (pintype "passive"))
      (node (ref "R17") (pin "P$1") (pinfunction "1_P$1") (pintype "passive"))
    )
    (net (code "63") (name "USB_S-") (class "Default")
      (node (ref "C30") (pin "P$1") (pinfunction "1_P$1") (pintype "passive"))
      (node (ref "CN2") (pin "P3") (pinfunction "D+_P3") (pintype "bidirectional"))
      (node (ref "D1") (pin "6") (pinfunction "I/O4_6") (pintype "bidirectional"))
      (node (ref "R19") (pin "P$2") (pinfunction "2_P$2") (pintype "passive"))
      (node (ref "R20") (pin "P$1") (pinfunction "1_P$1") (pintype "passive"))
    )
    (net (code "64") (name "VBAT") (class "Default")
      (node (ref "C18") (pin "P$1") (pinfunction "1_P$1") (pintype "passive"))
      (node (ref "CN1") (pin "P$4") (pinfunction "P$4_P$4") (pintype "bidirectional"))
      (node (ref "U3") (pin "1") (pinfunction "VIN_1") (pintype "bidirectional"))
    )
    (net (code "65") (name "VBIAS0") (class "Default")
      (node (ref "C2") (pin "P$1") (pinfunction "1_P$1") (pintype "passive"))
      (node (ref "U1") (pin "8") (pinfunction "VBIAS0_8") (pintype "bidirectional"))
    )
    (net (code "66") (name "VBIAS_CAP") (class "Default")
      (node (ref "C5") (pin "P$1") (pinfunction "1_P$1") (pintype "passive"))
      (node (ref "U1") (pin "31") (pinfunction "VBIAS_CAP_31") (pintype "bidirectional"))
    )
    (net (code "67") (name "VDD") (class "Default")
      (node (ref "CN1") (pin "P$2") (pinfunction "P$2_P$2") (pintype "bidirectional"))
      (node (ref "R37") (pin "P$1") (pinfunction "1_P$1") (pintype "passive"))
    )
    (net (code "68") (name "VREF_1V8") (class "Default")
      (node (ref "C4") (pin "P$1") (pinfunction "1_P$1") (pintype "passive"))
      (node (ref "U1") (pin "43") (pinfunction "VREF_1V8_43") (pintype "bidirectional"))
    )
    (net (code "69") (name "VREF_2V5") (class "Default")
      (node (ref "C3") (pin "P$1") (pinfunction "1_P$1") (pintype "passive"))
      (node (ref "U1") (pin "4") (pinfunction "VREF_2V5_4") (pintype "bidirectional"))
    )
    (net (code "70") (name "VZERO0") (class "Default")
      (node (ref "C1") (pin "P$1") (pinfunction "1_P$1") (pintype "passive"))
      (node (ref "U1") (pin "9") (pinfunction "VZERO0_9") (pintype "bidirectional"))
    )
    (net (code "71") (name "XTALI") (class "Default")
      (node (ref "C10") (pin "P$1") (pinfunction "1_P$1") (pintype "passive"))
      (node (ref "U1") (pin "11") (pinfunction "XTALI_11") (pintype "bidirectional"))
      (node (ref "Y1") (pin "P$1") (pinfunction "1_P$1") (pintype "passive"))
    )
    (net (code "72") (name "XTALO") (class "Default")
      (node (ref "C9") (pin "P$1") (pinfunction "1_P$1") (pintype "passive"))
      (node (ref "U1") (pin "12") (pinfunction "XTALO_12") (pintype "bidirectional"))
      (node (ref "Y1") (pin "P$3") (pinfunction "3_P$3") (pintype "passive"))
    )
    (net (code "73") (name "unconnected-(CN2-ID-PadP4)") (class "Default")
      (node (ref "CN2") (pin "P4") (pinfunction "ID_P4") (pintype "bidirectional"))
    )
    (net (code "74") (name "unconnected-(CN3-PadP$1)") (class "Default")
      (node (ref "CN3") (pin "P$1") (pinfunction "P$1_P$1") (pintype "bidirectional"))
    )
    (net (code "75") (name "unconnected-(CN3-PadP$2)") (class "Default")
      (node (ref "CN3") (pin "P$2") (pinfunction "P$2_P$2") (pintype "bidirectional"))
    )
    (net (code "76") (name "unconnected-(CN3-PadP$3)") (class "Default")
      (node (ref "CN3") (pin "P$3") (pinfunction "P$3_P$3") (pintype "bidirectional"))
    )
    (net (code "77") (name "unconnected-(CN3-PadP$4)") (class "Default")
      (node (ref "CN3") (pin "P$4") (pinfunction "P$4_P$4") (pintype "bidirectional"))
    )
    (net (code "78") (name "unconnected-(CN3-PadP$6)") (class "Default")
      (node (ref "CN3") (pin "P$6") (pinfunction "P$6_P$6") (pintype "bidirectional"))
    )
    (net (code "79") (name "unconnected-(U1-AFE4-Pad28)") (class "Default")
      (node (ref "U1") (pin "28") (pinfunction "AFE4_28") (pintype "bidirectional"))
    )
    (net (code "80") (name "unconnected-(U1-DNC1-Pad7)") (class "Default")
      (node (ref "U1") (pin "7") (pinfunction "DNC1_7") (pintype "bidirectional"))
    )
    (net (code "81") (name "unconnected-(U1-DNC2-Pad10)") (class "Default")
      (node (ref "U1") (pin "10") (pinfunction "DNC2_10") (pintype "bidirectional"))
    )
    (net (code "82") (name "unconnected-(U1-DNC3-Pad24)") (class "Default")
      (node (ref "U1") (pin "24") (pinfunction "DNC3_24") (pintype "bidirectional"))
    )
    (net (code "83") (name "unconnected-(U1-GPIO1-Pad20)") (class "Default")
      (node (ref "U1") (pin "20") (pinfunction "GPIO1_20") (pintype "bidirectional"))
    )
    (net (code "84") (name "unconnected-(U1-GPIO2-Pad21)") (class "Default")
      (node (ref "U1") (pin "21") (pinfunction "GPIO2_21") (pintype "bidirectional"))
    )
    (net (code "85") (name "unconnected-(U1-RC0_2-Pad1)") (class "Default")
      (node (ref "U1") (pin "1") (pinfunction "RC0_2_1") (pintype "bidirectional"))
    )
  )
)
